# Phase_3_1_Form_Factor_3.net
KiCad netlist of a schematic drawn in EAGLE
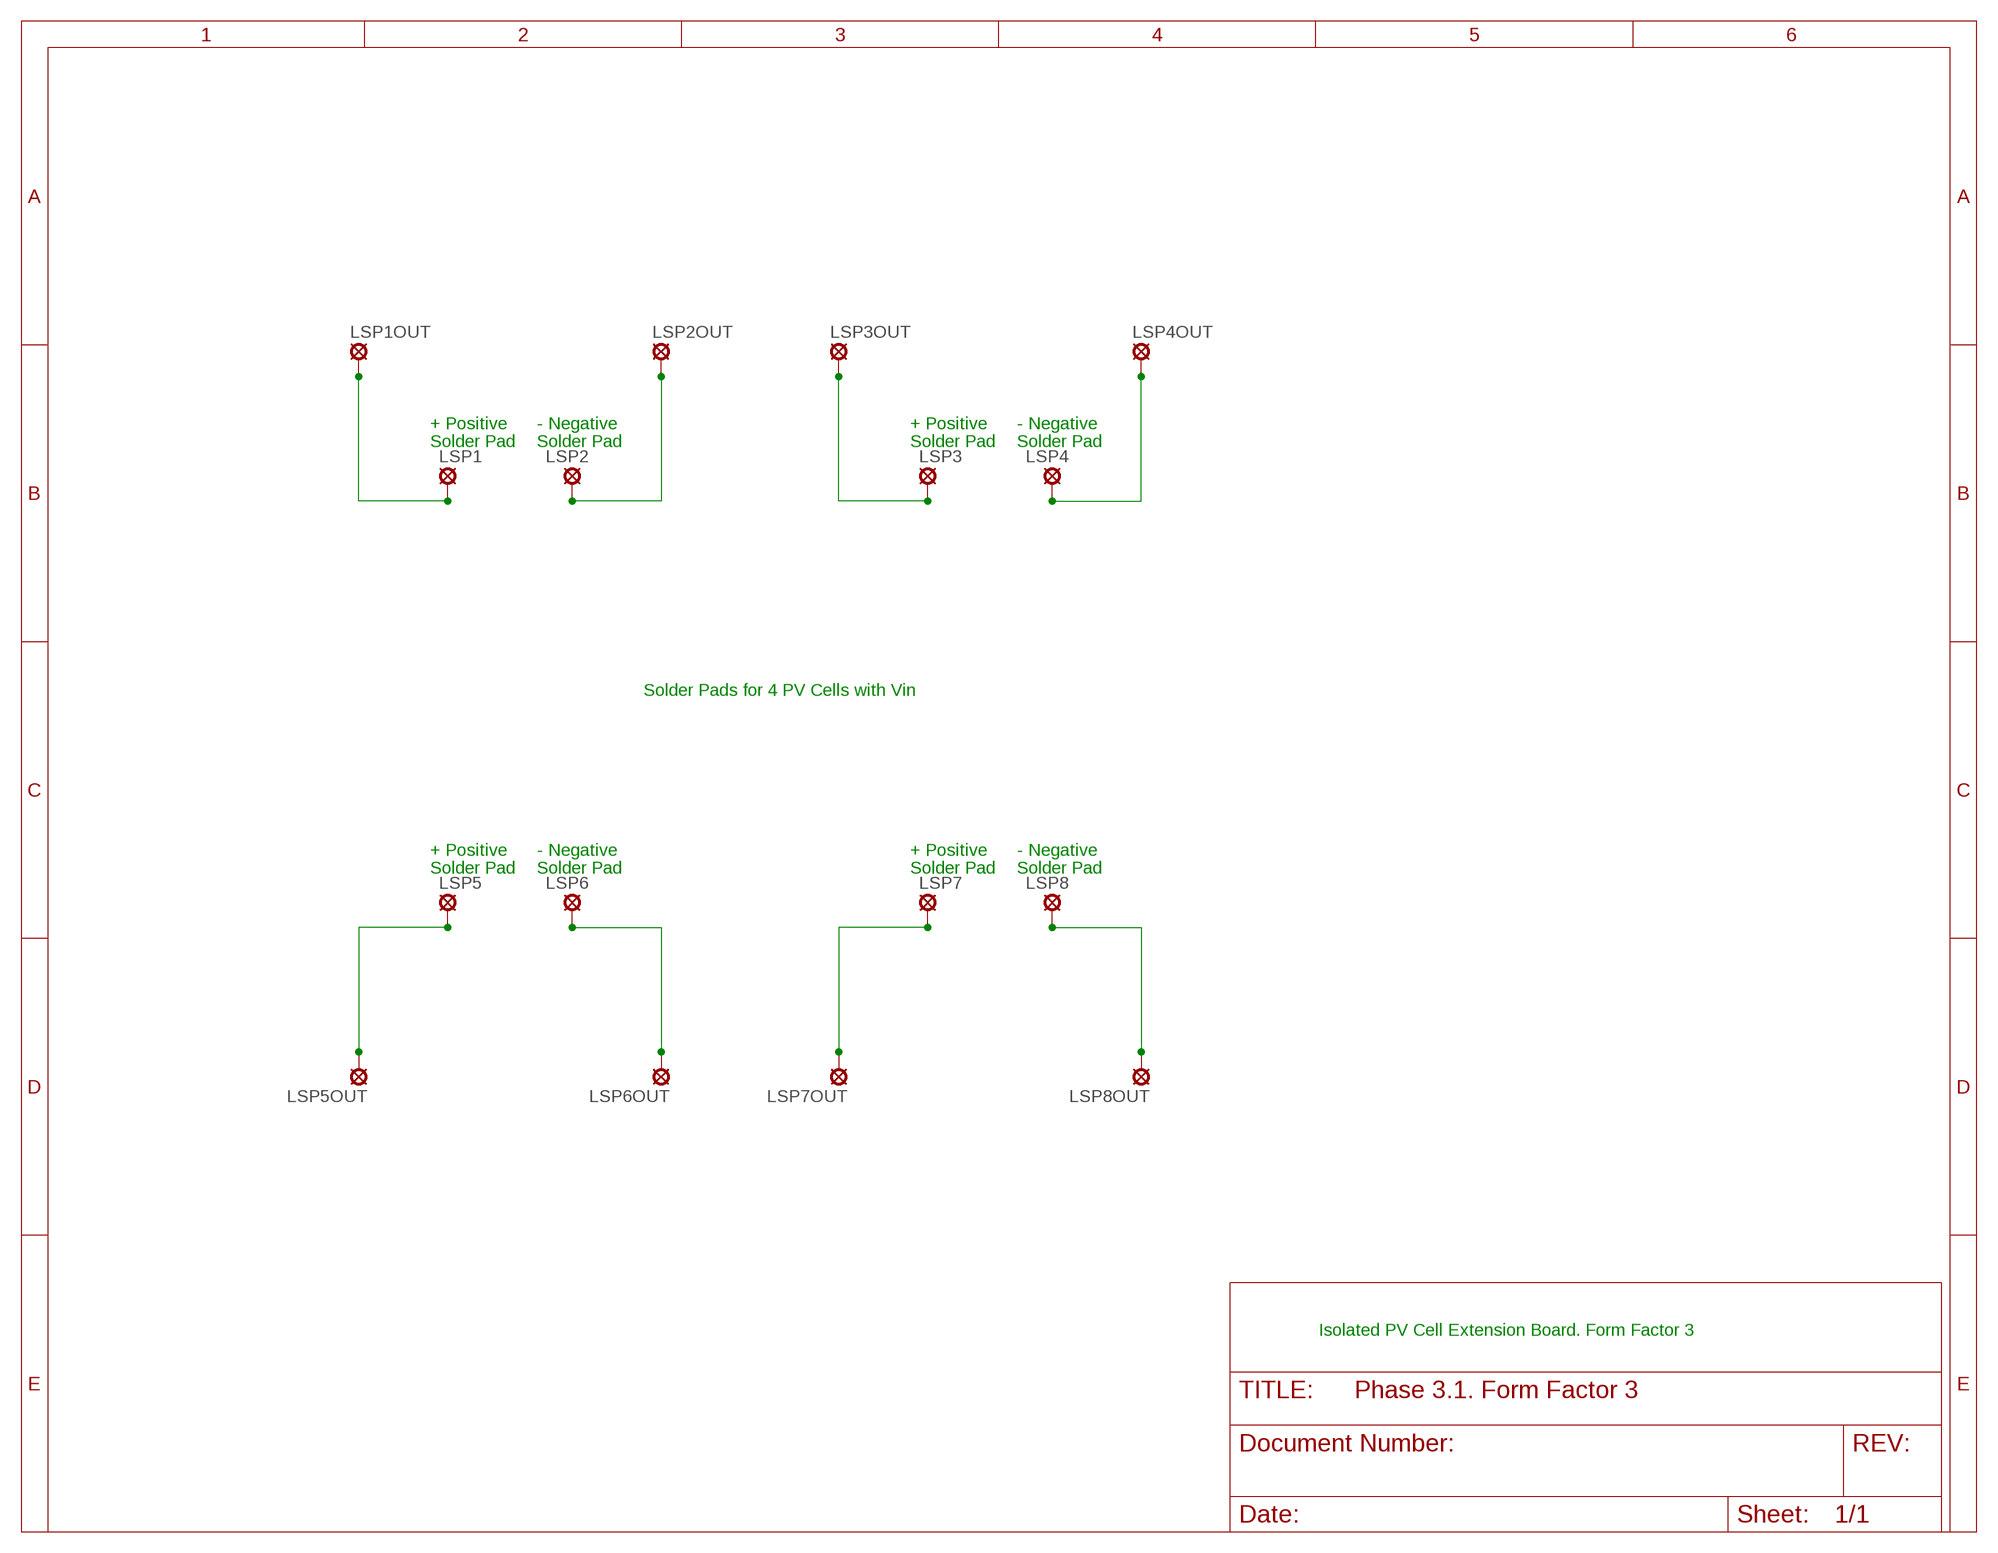
[diagram p0: schematic, sheet 1]

(export (version "E")
  (design (tool "Eeschema 10.0.6"))
  (components
    (comp (ref "LSP1")
      (value "LSP10")
      (footprint "eagle-import:LSP10")
      (libsource (lib "eagle-import") (part "LSP10"))
    )
    (comp (ref "LSP1OUT")
      (value "LSP10")
      (footprint "eagle-import:LSP10")
      (libsource (lib "eagle-import") (part "LSP10"))
    )
    (comp (ref "LSP2")
      (value "LSP10")
      (footprint "eagle-import:LSP10")
      (libsource (lib "eagle-import") (part "LSP10"))
    )
    (comp (ref "LSP2OUT")
      (value "LSP10")
      (footprint "eagle-import:LSP10")
      (libsource (lib "eagle-import") (part "LSP10"))
    )
    (comp (ref "LSP3")
      (value "LSP10")
      (footprint "eagle-import:LSP10")
      (libsource (lib "eagle-import") (part "LSP10"))
    )
    (comp (ref "LSP3OUT")
      (value "LSP10")
      (footprint "eagle-import:LSP10")
      (libsource (lib "eagle-import") (part "LSP10"))
    )
    (comp (ref "LSP4")
      (value "LSP10")
      (footprint "eagle-import:LSP10")
      (libsource (lib "eagle-import") (part "LSP10"))
    )
    (comp (ref "LSP4OUT")
      (value "LSP10")
      (footprint "eagle-import:LSP10")
      (libsource (lib "eagle-import") (part "LSP10"))
    )
    (comp (ref "LSP5")
      (value "LSP10")
      (footprint "eagle-import:LSP10")
      (libsource (lib "eagle-import") (part "LSP10"))
    )
    (comp (ref "LSP5OUT")
      (value "LSP10")
      (footprint "eagle-import:LSP10")
      (libsource (lib "eagle-import") (part "LSP10"))
    )
    (comp (ref "LSP6")
      (value "LSP10")
      (footprint "eagle-import:LSP10")
      (libsource (lib "eagle-import") (part "LSP10"))
    )
    (comp (ref "LSP6OUT")
      (value "LSP10")
      (footprint "eagle-import:LSP10")
      (libsource (lib "eagle-import") (part "LSP10"))
    )
    (comp (ref "LSP7")
      (value "LSP10")
      (footprint "eagle-import:LSP10")
      (libsource (lib "eagle-import") (part "LSP10"))
    )
    (comp (ref "LSP7OUT")
      (value "LSP10")
      (footprint "eagle-import:LSP10")
      (libsource (lib "eagle-import") (part "LSP10"))
    )
    (comp (ref "LSP8")
      (value "LSP10")
      (footprint "eagle-import:LSP10")
      (libsource (lib "eagle-import") (part "LSP10"))
    )
    (comp (ref "LSP8OUT")
      (value "LSP10")
      (footprint "eagle-import:LSP10")
      (libsource (lib "eagle-import") (part "LSP10"))
    )
  )
  (nets
    (net (code "1") (name "Net-(LSP1-PadMP)") (class "Default")
      (node (ref "LSP1") (pin "MP") (pinfunction "MP_MP") (pintype "passive"))
      (node (ref "LSP1OUT") (pin "MP") (pinfunction "MP_MP") (pintype "passive"))
    )
    (net (code "2") (name "Net-(LSP2-PadMP)") (class "Default")
      (node (ref "LSP2") (pin "MP") (pinfunction "MP_MP") (pintype "passive"))
      (node (ref "LSP2OUT") (pin "MP") (pinfunction "MP_MP") (pintype "passive"))
    )
    (net (code "3") (name "Net-(LSP3-PadMP)") (class "Default")
      (node (ref "LSP3") (pin "MP") (pinfunction "MP_MP") (pintype "passive"))
      (node (ref "LSP3OUT") (pin "MP") (pinfunction "MP_MP") (pintype "passive"))
    )
    (net (code "4") (name "Net-(LSP4-PadMP)") (class "Default")
      (node (ref "LSP4") (pin "MP") (pinfunction "MP_MP") (pintype "passive"))
      (node (ref "LSP4OUT") (pin "MP") (pinfunction "MP_MP") (pintype "passive"))
    )
    (net (code "5") (name "Net-(LSP5-PadMP)") (class "Default")
      (node (ref "LSP5") (pin "MP") (pinfunction "MP_MP") (pintype "passive"))
      (node (ref "LSP5OUT") (pin "MP") (pinfunction "MP_MP") (pintype "passive"))
    )
    (net (code "6") (name "Net-(LSP6-PadMP)") (class "Default")
      (node (ref "LSP6") (pin "MP") (pinfunction "MP_MP") (pintype "passive"))
      (node (ref "LSP6OUT") (pin "MP") (pinfunction "MP_MP") (pintype "passive"))
    )
    (net (code "7") (name "Net-(LSP7-PadMP)") (class "Default")
      (node (ref "LSP7") (pin "MP") (pinfunction "MP_MP") (pintype "passive"))
      (node (ref "LSP7OUT") (pin "MP") (pinfunction "MP_MP") (pintype "passive"))
    )
    (net (code "8") (name "Net-(LSP8-PadMP)") (class "Default")
      (node (ref "LSP8") (pin "MP") (pinfunction "MP_MP") (pintype "passive"))
      (node (ref "LSP8OUT") (pin "MP") (pinfunction "MP_MP") (pintype "passive"))
    )
  )
)
